# Analog.net
KiCad netlist of a schematic drawn in Altium Designer
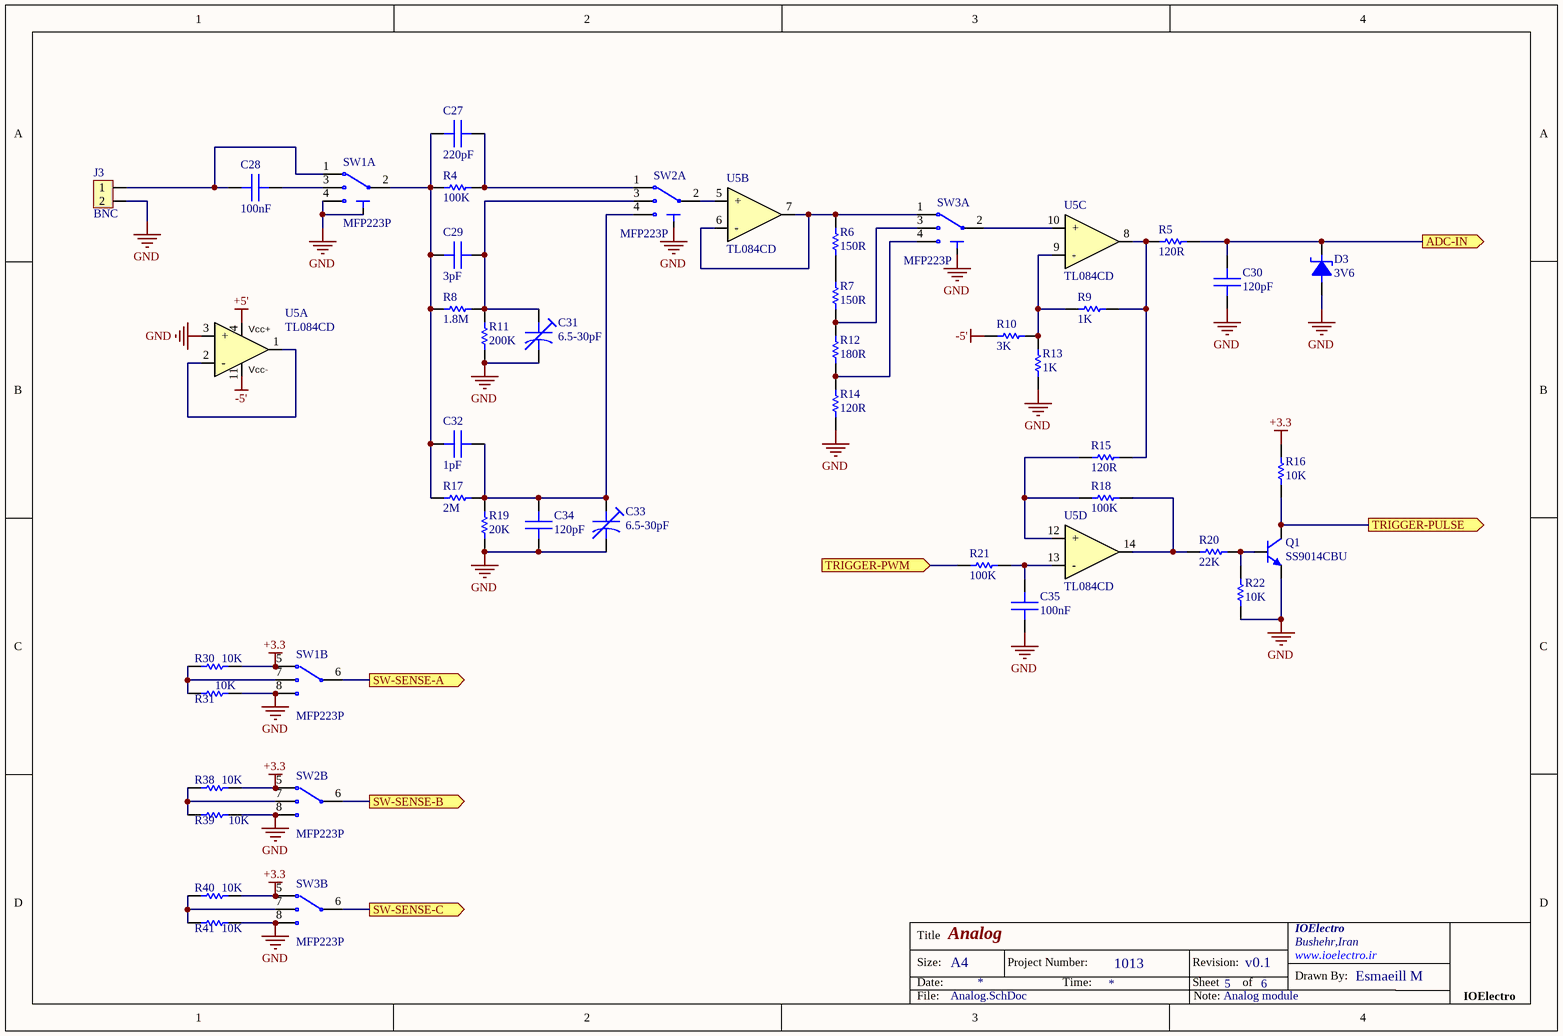
[diagram p0: Analog.SchDoc]

(export (version "E")
  (design (tool "Eeschema 10.0.6"))
  (components
    (comp (ref "C27")
      (value "220pF")
      (footprint "C-BP-Ceramic-DIP")
      (description "Ceramic Disk Capacitor 50V")
      (libsource (lib "IOElectro") (part "CAP"))
    )
    (comp (ref "C28")
      (value "100nF")
      (footprint "C-BP-Ceramic-DIP")
      (description "Ceramic Disk Capacitor 50V")
      (libsource (lib "IOElectro") (part "CAP"))
    )
    (comp (ref "C29")
      (value "3pF")
      (footprint "C-BP-Ceramic-DIP")
      (description "Ceramic Disk Capacitor 50V")
      (libsource (lib "IOElectro") (part "CAP"))
    )
    (comp (ref "C30")
      (value "120pF")
      (footprint "C-BP-Ceramic-DIP")
      (description "Ceramic Disk Capacitor 50V")
      (libsource (lib "IOElectro") (part "CAP"))
    )
    (comp (ref "C31")
      (value "6.5-30pF")
      (footprint "C-TR-DIP_5mm")
      (description "Trimmer / Variable Capacitors 6.5-30pF 100V 85 DEG")
      (fields
        (field (name "MANUFACTURER") "Sprague Goodman")
        (field (name "MANUFACTURER PART NUMBER") "GKG30015")
      )
      (libsource (lib "IOElectro") (part "GKG30015"))
    )
    (comp (ref "C32")
      (value "1pF")
      (footprint "C-BP-Ceramic-DIP")
      (description "Ceramic Disk Capacitor 50V")
      (libsource (lib "IOElectro") (part "CAP"))
    )
    (comp (ref "C33")
      (value "6.5-30pF")
      (footprint "C-TR-DIP_5mm")
      (description "Trimmer / Variable Capacitors 6.5-30pF 100V 85 DEG")
      (fields
        (field (name "MANUFACTURER") "Sprague Goodman")
        (field (name "MANUFACTURER PART NUMBER") "GKG30015")
      )
      (libsource (lib "IOElectro") (part "GKG30015"))
    )
    (comp (ref "C34")
      (value "120pF")
      (footprint "C-BP-Ceramic-DIP")
      (description "Ceramic Disk Capacitor 50V")
      (libsource (lib "IOElectro") (part "CAP"))
    )
    (comp (ref "C35")
      (value "100nF")
      (footprint "C-BP-Ceramic-DIP")
      (description "Ceramic Disk Capacitor 50V")
      (libsource (lib "IOElectro") (part "CAP"))
    )
    (comp (ref "D3")
      (value "3V6")
      (footprint "SOD80")
      (description "SMD MiniMELF")
      (libsource (lib "IOElectro") (part "DIODE-Z"))
    )
    (comp (ref "J3")
      (value "BNC")
      (footprint "PH-1X2-N3D")
      (description "PIN HEADER 1x2 2.56mm")
      (libsource (lib "Schlib") (part "PH-1X2"))
    )
    (comp (ref "Q1")
      (value "SS9014CBU")
      (footprint "TO-92")
      (description "Bipolar (BJT) Single Transistor, NPN, 45 V, 270 MHz, 450 mW, 100 mA, 200")
      (fields (field (name "MANUFACTURER") "ON Semiconductor"))
      (libsource (lib "IOElectro") (part "SS9014CBU"))
    )
    (comp (ref "R4")
      (value "100K")
      (footprint "R-1/4W-DIP-Blue")
      (description "Resistor DIP 1/4W 1%")
      (libsource (lib "IOElectro") (part "RES"))
    )
    (comp (ref "R5")
      (value "120R")
      (footprint "R-1/4W-DIP-Blue")
      (description "Resistor DIP 1/4W 1%")
      (libsource (lib "IOElectro") (part "RES"))
    )
    (comp (ref "R6")
      (value "150R")
      (footprint "R-1/4W-DIP-Blue")
      (description "Resistor DIP 1/4W 1%")
      (libsource (lib "IOElectro") (part "RES"))
    )
    (comp (ref "R7")
      (value "150R")
      (footprint "R-1/4W-DIP-Blue")
      (description "Resistor DIP 1/4W 1%")
      (libsource (lib "IOElectro") (part "RES"))
    )
    (comp (ref "R8")
      (value "1.8M")
      (footprint "R-1/4W-DIP-Blue")
      (description "Resistor DIP 1/4W 1%")
      (libsource (lib "IOElectro") (part "RES"))
    )
    (comp (ref "R9")
      (value "1K")
      (footprint "R-1/4W-DIP-Blue")
      (description "Resistor DIP 1/4W 1%")
      (libsource (lib "IOElectro") (part "RES"))
    )
    (comp (ref "R10")
      (value "3K")
      (footprint "R-1/4W-DIP-Blue")
      (description "Resistor DIP 1/4W 1%")
      (libsource (lib "IOElectro") (part "RES"))
    )
    (comp (ref "R11")
      (value "200K")
      (footprint "R-1/4W-DIP-Blue")
      (description "Resistor DIP 1/4W 1%")
      (libsource (lib "IOElectro") (part "RES"))
    )
    (comp (ref "R12")
      (value "180R")
      (footprint "R-1/4W-DIP-Blue")
      (description "Resistor DIP 1/4W 1%")
      (libsource (lib "IOElectro") (part "RES"))
    )
    (comp (ref "R13")
      (value "1K")
      (footprint "R-1/4W-DIP-Blue")
      (description "Resistor DIP 1/4W 1%")
      (libsource (lib "IOElectro") (part "RES"))
    )
    (comp (ref "R14")
      (value "120R")
      (footprint "R-1/4W-DIP-Blue")
      (description "Resistor DIP 1/4W 1%")
      (libsource (lib "IOElectro") (part "RES"))
    )
    (comp (ref "R15")
      (value "120R")
      (footprint "R-1/4W-DIP-Blue")
      (description "Resistor DIP 1/4W 1%")
      (libsource (lib "IOElectro") (part "RES"))
    )
    (comp (ref "R16")
      (value "10K")
      (footprint "R-0805")
      (description "0805")
      (libsource (lib "IOElectro") (part "RES"))
    )
    (comp (ref "R17")
      (value "2M")
      (footprint "R-1/4W-DIP-Blue")
      (description "Resistor DIP 1/4W 1%")
      (libsource (lib "IOElectro") (part "RES"))
    )
    (comp (ref "R18")
      (value "100K")
      (footprint "R-1/4W-DIP-Blue")
      (description "Resistor DIP 1/4W 1%")
      (libsource (lib "IOElectro") (part "RES"))
    )
    (comp (ref "R19")
      (value "20K")
      (footprint "R-1/4W-DIP-Blue")
      (description "Resistor DIP 1/4W 1%")
      (libsource (lib "IOElectro") (part "RES"))
    )
    (comp (ref "R20")
      (value "22K")
      (footprint "R-0805")
      (description "0805")
      (libsource (lib "IOElectro") (part "RES"))
    )
    (comp (ref "R21")
      (value "100K")
      (footprint "R-1/4W-DIP-Blue")
      (description "Resistor DIP 1/4W 1%")
      (libsource (lib "IOElectro") (part "RES"))
    )
    (comp (ref "R22")
      (value "10K")
      (footprint "R-0805")
      (description "0805")
      (libsource (lib "IOElectro") (part "RES"))
    )
    (comp (ref "R30")
      (value "10K")
      (footprint "R-0805")
      (description "0805")
      (libsource (lib "IOElectro") (part "RES"))
    )
    (comp (ref "R31")
      (value "10K")
      (footprint "R-0805")
      (description "0805")
      (libsource (lib "IOElectro") (part "RES"))
    )
    (comp (ref "R38")
      (value "10K")
      (footprint "R-0805")
      (description "0805")
      (libsource (lib "IOElectro") (part "RES"))
    )
    (comp (ref "R39")
      (value "10K")
      (footprint "R-0805")
      (description "0805")
      (libsource (lib "IOElectro") (part "RES"))
    )
    (comp (ref "R40")
      (value "10K")
      (footprint "R-0805")
      (description "0805")
      (libsource (lib "IOElectro") (part "RES"))
    )
    (comp (ref "R41")
      (value "10K")
      (footprint "R-0805")
      (description "0805")
      (libsource (lib "IOElectro") (part "RES"))
    )
    (comp (ref "SW1")
      (value "MFP223P")
      (footprint "MFP223P")
      (description "Switch Slide ON ON ON Extended Top Slide 0.35A 30VDC 10000Cycle PC Pins Bracket Mount/Through Hole")
      (fields (field (name "MANUFACTURER") "Knitter-Switch"))
      (libsource (lib "Schlib") (part "MFP223P"))
    )
    (comp (ref "SW2")
      (value "MFP223P")
      (footprint "MFP223P")
      (description "Switch Slide ON ON ON Extended Top Slide 0.35A 30VDC 10000Cycle PC Pins Bracket Mount/Through Hole")
      (fields (field (name "MANUFACTURER") "Knitter-Switch"))
      (libsource (lib "IOElectro") (part "MFP223P"))
    )
    (comp (ref "SW3")
      (value "MFP223P")
      (footprint "MFP223P")
      (description "Switch Slide ON ON ON Extended Top Slide 0.35A 30VDC 10000Cycle PC Pins Bracket Mount/Through Hole")
      (fields (field (name "MANUFACTURER") "Knitter-Switch"))
      (libsource (lib "IOElectro") (part "MFP223P"))
    )
    (comp (ref "U5")
      (value "TL084CD")
      (footprint "SO-14")
      (description "IC OPAMP JFET 4MHZ 14SO")
      (fields (field (name "MANUFACTURER") "STMicroelectronics"))
      (libsource (lib "IOElectro") (part "TL084CD"))
    )
  )
  (nets
    (net (code "1") (name "+3.3") (class "Default")
      (node (ref "R16") (pin "2") (pinfunction "2_2") (pintype "passive"))
      (node (ref "R30") (pin "1") (pinfunction "1_1") (pintype "passive"))
      (node (ref "R38") (pin "1") (pinfunction "1_1") (pintype "passive"))
      (node (ref "R40") (pin "1") (pinfunction "1_1") (pintype "passive"))
      (node (ref "SW1") (pin "5") (pinfunction "5_5") (pintype "passive"))
      (node (ref "SW2") (pin "5") (pinfunction "5_5") (pintype "passive"))
      (node (ref "SW3") (pin "5") (pinfunction "5_5") (pintype "passive"))
    )
    (net (code "2") (name "+5'") (class "Default")
      (node (ref "U5") (pin "4") (pinfunction "Vcc+_4") (pintype "passive"))
    )
    (net (code "3") (name "-5'") (class "Default")
      (node (ref "R10") (pin "1") (pinfunction "1_1") (pintype "passive"))
      (node (ref "U5") (pin "11") (pinfunction "Vcc-_11") (pintype "passive"))
    )
    (net (code "4") (name "/ADC-IN") (class "Default")
      (node (ref "C30") (pin "1") (pinfunction "1_1") (pintype "passive"))
      (node (ref "D3") (pin "K") (pinfunction "K_K") (pintype "passive"))
      (node (ref "R5") (pin "1") (pinfunction "1_1") (pintype "passive"))
    )
    (net (code "5") (name "/SW-SENSE-A") (class "Default")
      (node (ref "SW1") (pin "6") (pinfunction "6_6") (pintype "passive"))
    )
    (net (code "6") (name "/SW-SENSE-B") (class "Default")
      (node (ref "SW2") (pin "6") (pinfunction "6_6") (pintype "passive"))
    )
    (net (code "7") (name "/SW-SENSE-C") (class "Default")
      (node (ref "SW3") (pin "6") (pinfunction "6_6") (pintype "passive"))
    )
    (net (code "8") (name "/TRIGGER-PULSE") (class "Default")
      (node (ref "Q1") (pin "3") (pinfunction "C_3") (pintype "passive"))
      (node (ref "R16") (pin "1") (pinfunction "1_1") (pintype "passive"))
    )
    (net (code "9") (name "/TRIGGER-PWM") (class "Default")
      (node (ref "R21") (pin "2") (pinfunction "2_2") (pintype "passive"))
    )
    (net (code "10") (name "GND") (class "Default")
      (node (ref "C30") (pin "2") (pinfunction "2_2") (pintype "passive"))
      (node (ref "C31") (pin "K") (pinfunction "K_K") (pintype "passive"))
      (node (ref "C33") (pin "K") (pinfunction "K_K") (pintype "passive"))
      (node (ref "C34") (pin "2") (pinfunction "2_2") (pintype "passive"))
      (node (ref "C35") (pin "2") (pinfunction "2_2") (pintype "passive"))
      (node (ref "D3") (pin "A") (pinfunction "A_A") (pintype "passive"))
      (node (ref "J3") (pin "2") (pinfunction "2_2") (pintype "passive"))
      (node (ref "Q1") (pin "1") (pinfunction "E_1") (pintype "passive"))
      (node (ref "R11") (pin "1") (pinfunction "1_1") (pintype "passive"))
      (node (ref "R13") (pin "2") (pinfunction "2_2") (pintype "passive"))
      (node (ref "R14") (pin "1") (pinfunction "1_1") (pintype "passive"))
      (node (ref "R19") (pin "1") (pinfunction "1_1") (pintype "passive"))
      (node (ref "R22") (pin "1") (pinfunction "1_1") (pintype "passive"))
      (node (ref "R31") (pin "1") (pinfunction "1_1") (pintype "passive"))
      (node (ref "R39") (pin "1") (pinfunction "1_1") (pintype "passive"))
      (node (ref "R41") (pin "1") (pinfunction "1_1") (pintype "passive"))
      (node (ref "SW1") (pin "0") (pinfunction "0_0") (pintype "passive"))
      (node (ref "SW1") (pin "4") (pinfunction "4_4") (pintype "passive"))
      (node (ref "SW1") (pin "8") (pinfunction "5_8") (pintype "passive"))
      (node (ref "SW2") (pin "0") (pinfunction "0_0") (pintype "passive"))
      (node (ref "SW2") (pin "8") (pinfunction "5_8") (pintype "passive"))
      (node (ref "SW3") (pin "0") (pinfunction "0_0") (pintype "passive"))
      (node (ref "SW3") (pin "8") (pinfunction "5_8") (pintype "passive"))
      (node (ref "U5") (pin "3") (pinfunction "+_3") (pintype "passive"))
    )
    (net (code "11") (name "Net-(C27-Pad1)") (class "Default")
      (node (ref "C27") (pin "1") (pinfunction "1_1") (pintype "passive"))
      (node (ref "R4") (pin "2") (pinfunction "2_2") (pintype "passive"))
      (node (ref "SW2") (pin "1") (pinfunction "1_1") (pintype "passive"))
    )
    (net (code "12") (name "Net-(C27-Pad2)") (class "Default")
      (node (ref "C27") (pin "2") (pinfunction "2_2") (pintype "passive"))
      (node (ref "C29") (pin "2") (pinfunction "2_2") (pintype "passive"))
      (node (ref "C32") (pin "2") (pinfunction "2_2") (pintype "passive"))
      (node (ref "R17") (pin "1") (pinfunction "1_1") (pintype "passive"))
      (node (ref "R4") (pin "1") (pinfunction "1_1") (pintype "passive"))
      (node (ref "R8") (pin "1") (pinfunction "1_1") (pintype "passive"))
      (node (ref "SW1") (pin "2") (pinfunction "2_2") (pintype "passive"))
    )
    (net (code "13") (name "Net-(C28-Pad1)") (class "Default")
      (node (ref "C28") (pin "1") (pinfunction "1_1") (pintype "passive"))
      (node (ref "SW1") (pin "3") (pinfunction "3_3") (pintype "passive"))
    )
    (net (code "14") (name "Net-(C28-Pad2)") (class "Default")
      (node (ref "C28") (pin "2") (pinfunction "2_2") (pintype "passive"))
      (node (ref "J3") (pin "1") (pinfunction "1_1") (pintype "passive"))
      (node (ref "SW1") (pin "1") (pinfunction "1_1") (pintype "passive"))
    )
    (net (code "15") (name "Net-(C29-Pad1)") (class "Default")
      (node (ref "C29") (pin "1") (pinfunction "1_1") (pintype "passive"))
      (node (ref "C31") (pin "A") (pinfunction "A_A") (pintype "passive"))
      (node (ref "R11") (pin "2") (pinfunction "2_2") (pintype "passive"))
      (node (ref "R8") (pin "2") (pinfunction "2_2") (pintype "passive"))
      (node (ref "SW2") (pin "3") (pinfunction "3_3") (pintype "passive"))
    )
    (net (code "16") (name "Net-(C32-Pad1)") (class "Default")
      (node (ref "C32") (pin "1") (pinfunction "1_1") (pintype "passive"))
      (node (ref "C33") (pin "A") (pinfunction "A_A") (pintype "passive"))
      (node (ref "C34") (pin "1") (pinfunction "1_1") (pintype "passive"))
      (node (ref "R17") (pin "2") (pinfunction "2_2") (pintype "passive"))
      (node (ref "R19") (pin "2") (pinfunction "2_2") (pintype "passive"))
      (node (ref "SW2") (pin "4") (pinfunction "4_4") (pintype "passive"))
    )
    (net (code "17") (name "Net-(Q1-B)") (class "Default")
      (node (ref "Q1") (pin "2") (pinfunction "B_2") (pintype "passive"))
      (node (ref "R20") (pin "1") (pinfunction "1_1") (pintype "passive"))
      (node (ref "R22") (pin "2") (pinfunction "2_2") (pintype "passive"))
    )
    (net (code "18") (name "Net-(R6-Pad1)") (class "Default")
      (node (ref "R6") (pin "1") (pinfunction "1_1") (pintype "passive"))
      (node (ref "R7") (pin "2") (pinfunction "2_2") (pintype "passive"))
    )
    (net (code "19") (name "Net-(R12-Pad1)") (class "Default")
      (node (ref "R12") (pin "1") (pinfunction "1_1") (pintype "passive"))
      (node (ref "R14") (pin "2") (pinfunction "2_2") (pintype "passive"))
      (node (ref "SW3") (pin "4") (pinfunction "4_4") (pintype "passive"))
    )
    (net (code "20") (name "Net-(R12-Pad2)") (class "Default")
      (node (ref "R12") (pin "2") (pinfunction "2_2") (pintype "passive"))
      (node (ref "R7") (pin "1") (pinfunction "1_1") (pintype "passive"))
      (node (ref "SW3") (pin "3") (pinfunction "3_3") (pintype "passive"))
    )
    (net (code "21") (name "Net-(R30-Pad2)") (class "Default")
      (node (ref "R30") (pin "2") (pinfunction "2_2") (pintype "passive"))
      (node (ref "R31") (pin "2") (pinfunction "2_2") (pintype "passive"))
      (node (ref "SW1") (pin "7") (pinfunction "7_7") (pintype "passive"))
    )
    (net (code "22") (name "Net-(R38-Pad2)") (class "Default")
      (node (ref "R38") (pin "2") (pinfunction "2_2") (pintype "passive"))
      (node (ref "R39") (pin "2") (pinfunction "2_2") (pintype "passive"))
      (node (ref "SW2") (pin "7") (pinfunction "7_7") (pintype "passive"))
    )
    (net (code "23") (name "Net-(R40-Pad2)") (class "Default")
      (node (ref "R40") (pin "2") (pinfunction "2_2") (pintype "passive"))
      (node (ref "R41") (pin "2") (pinfunction "2_2") (pintype "passive"))
      (node (ref "SW3") (pin "7") (pinfunction "7_7") (pintype "passive"))
    )
    (net (code "24") (name "Net-(U5A--)") (class "Default")
      (node (ref "U5") (pin "1") (pinfunction "O_1") (pintype "passive"))
      (node (ref "U5") (pin "2") (pinfunction "-_2") (pintype "passive"))
    )
    (net (code "25") (name "Net-(U5B-+)") (class "Default")
      (node (ref "SW2") (pin "2") (pinfunction "2_2") (pintype "passive"))
      (node (ref "U5") (pin "5") (pinfunction "+_5") (pintype "passive"))
    )
    (net (code "26") (name "Net-(U5B--)") (class "Default")
      (node (ref "R6") (pin "2") (pinfunction "2_2") (pintype "passive"))
      (node (ref "SW3") (pin "1") (pinfunction "1_1") (pintype "passive"))
      (node (ref "U5") (pin "6") (pinfunction "-_6") (pintype "passive"))
      (node (ref "U5") (pin "7") (pinfunction "O_7") (pintype "passive"))
    )
    (net (code "27") (name "Net-(U5C-+)") (class "Default")
      (node (ref "SW3") (pin "2") (pinfunction "2_2") (pintype "passive"))
      (node (ref "U5") (pin "10") (pinfunction "+_10") (pintype "passive"))
    )
    (net (code "28") (name "Net-(U5C--)") (class "Default")
      (node (ref "R10") (pin "2") (pinfunction "2_2") (pintype "passive"))
      (node (ref "R13") (pin "1") (pinfunction "1_1") (pintype "passive"))
      (node (ref "R9") (pin "2") (pinfunction "2_2") (pintype "passive"))
      (node (ref "U5") (pin "9") (pinfunction "-_9") (pintype "passive"))
    )
    (net (code "29") (name "Net-(U5C-O)") (class "Default")
      (node (ref "R15") (pin "1") (pinfunction "1_1") (pintype "passive"))
      (node (ref "R5") (pin "2") (pinfunction "2_2") (pintype "passive"))
      (node (ref "R9") (pin "1") (pinfunction "1_1") (pintype "passive"))
      (node (ref "U5") (pin "8") (pinfunction "O_8") (pintype "passive"))
    )
    (net (code "30") (name "Net-(U5D-+)") (class "Default")
      (node (ref "R15") (pin "2") (pinfunction "2_2") (pintype "passive"))
      (node (ref "R18") (pin "2") (pinfunction "2_2") (pintype "passive"))
      (node (ref "U5") (pin "12") (pinfunction "+_12") (pintype "passive"))
    )
    (net (code "31") (name "Net-(U5D--)") (class "Default")
      (node (ref "C35") (pin "1") (pinfunction "1_1") (pintype "passive"))
      (node (ref "R21") (pin "1") (pinfunction "1_1") (pintype "passive"))
      (node (ref "U5") (pin "13") (pinfunction "-_13") (pintype "passive"))
    )
    (net (code "32") (name "Net-(U5D-O)") (class "Default")
      (node (ref "R18") (pin "1") (pinfunction "1_1") (pintype "passive"))
      (node (ref "R20") (pin "2") (pinfunction "2_2") (pintype "passive"))
      (node (ref "U5") (pin "14") (pinfunction "O_14") (pintype "passive"))
    )
  )
)
